# SCH_Auto-tune-FM-reciever-1_00_2024-02-2.net
KiCad netlist of a schematic drawn in EasyEDA
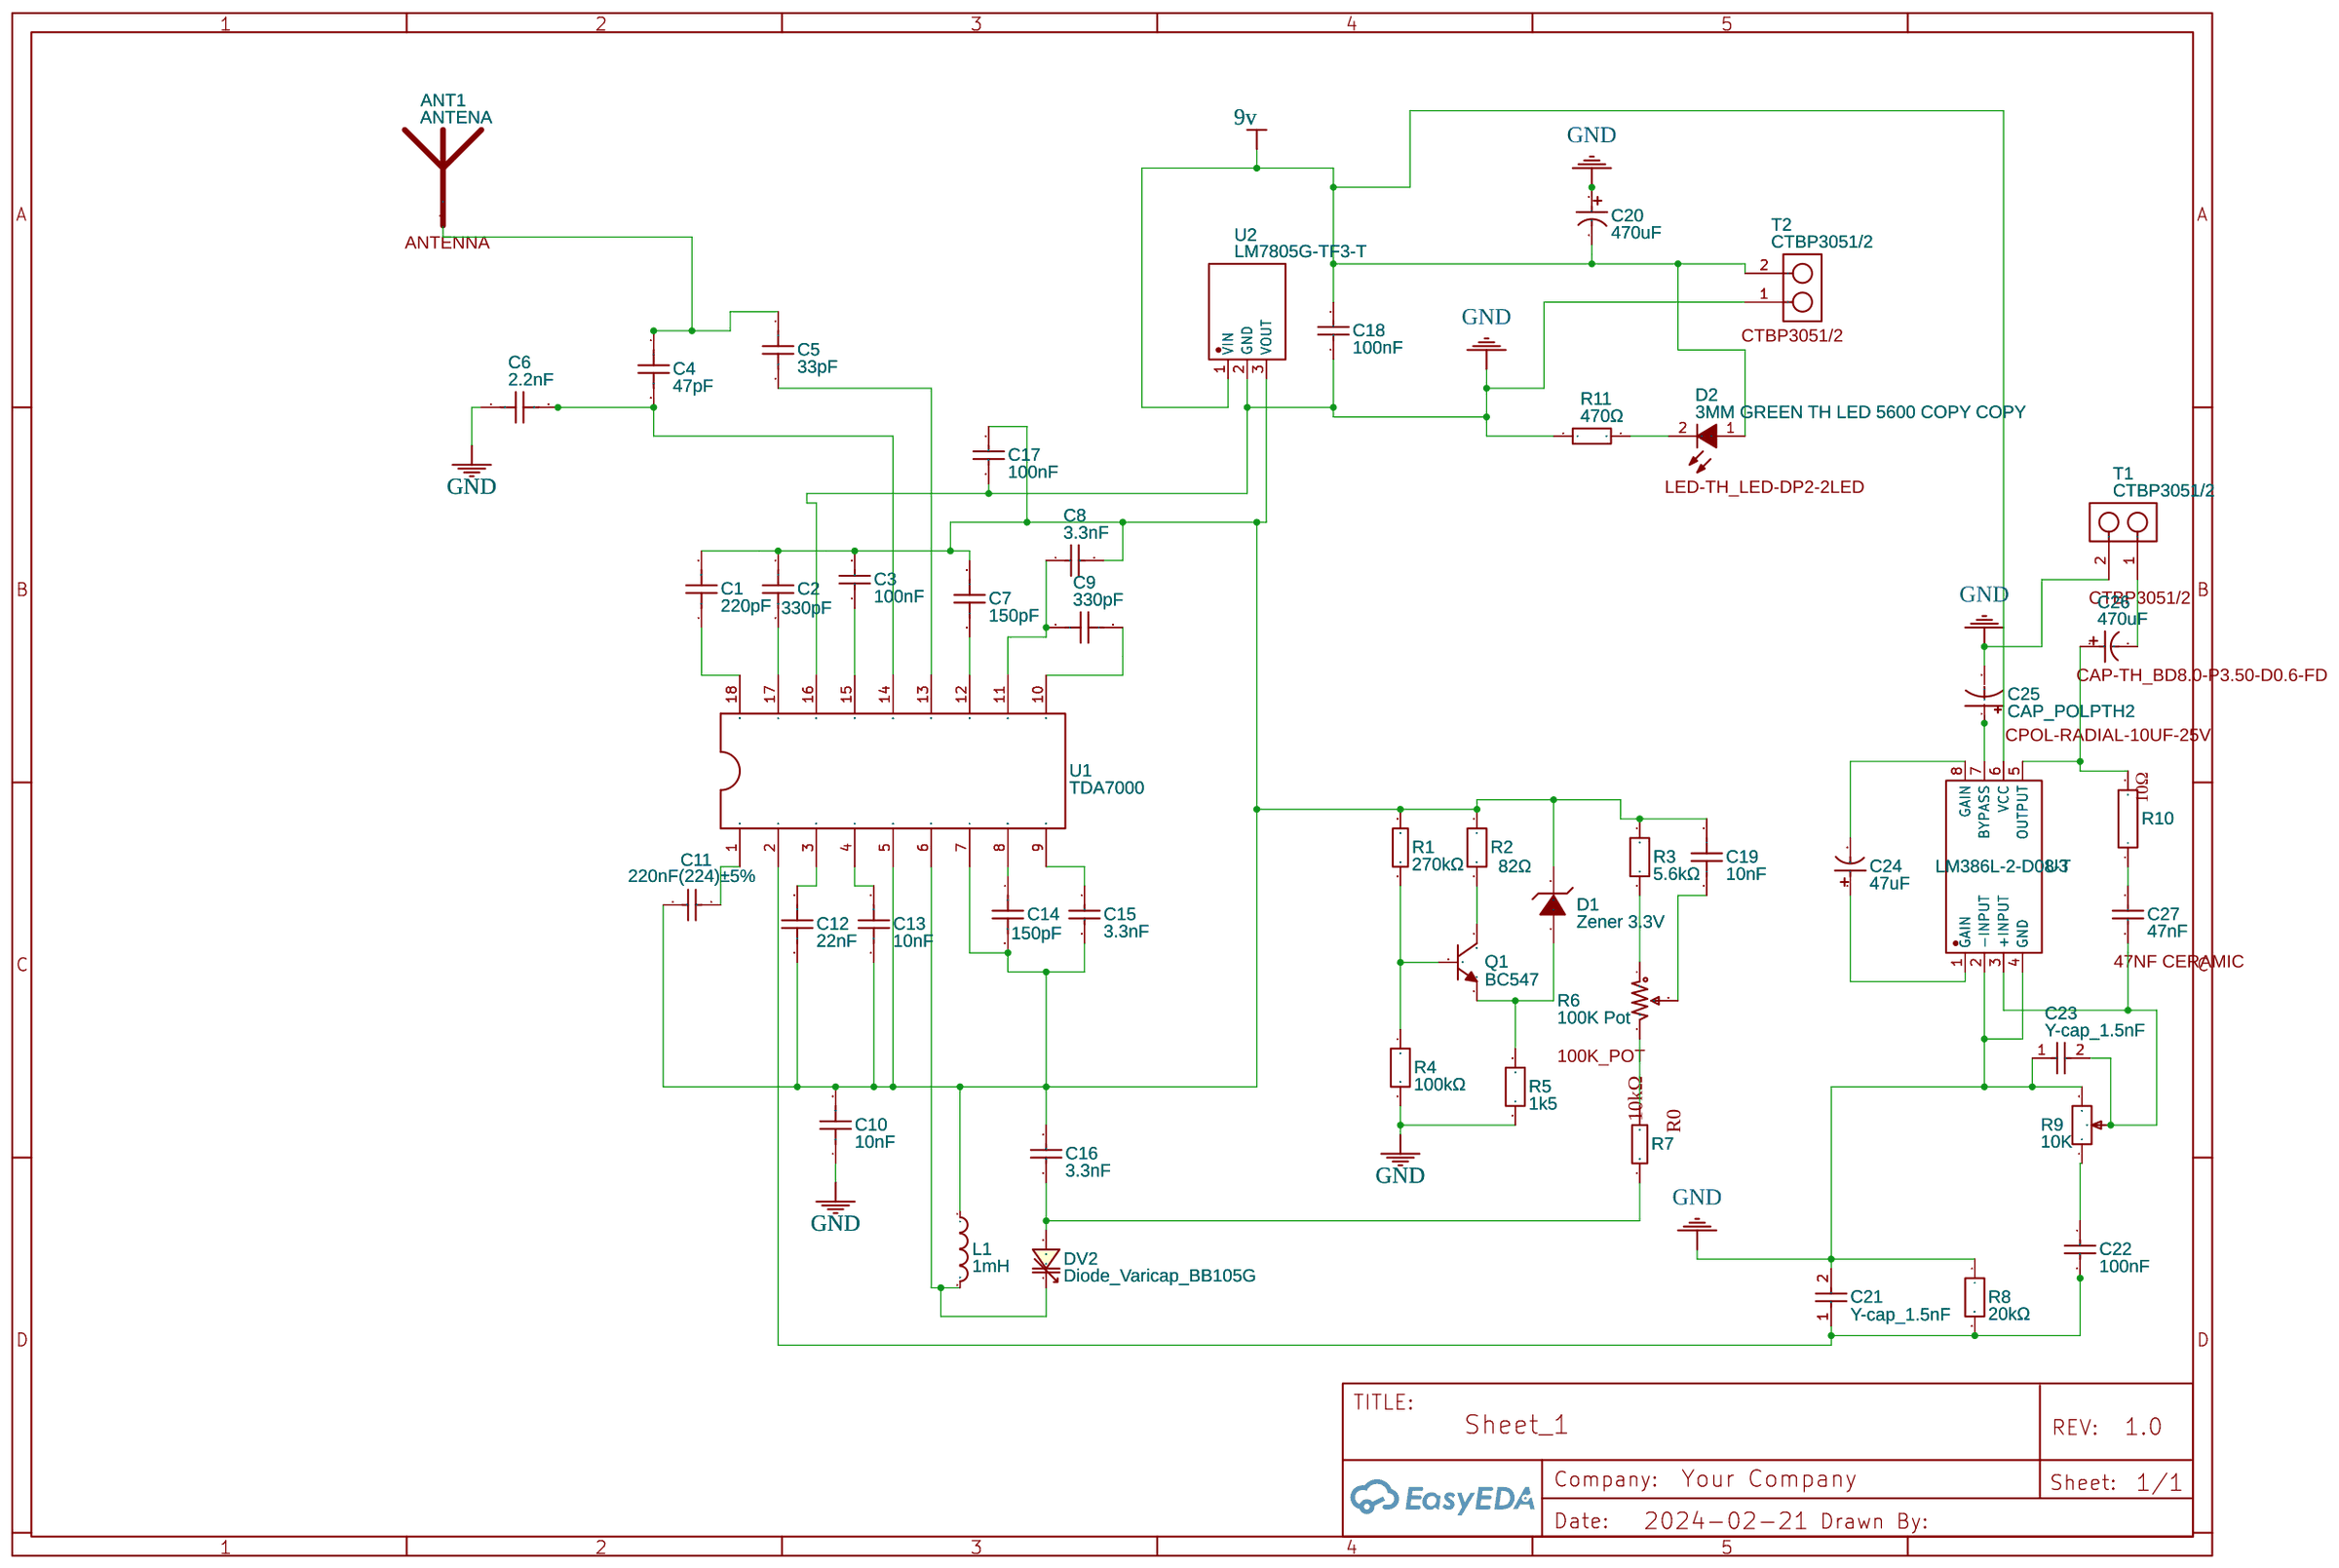
[diagram p0: schematic sheet]

(export (version "E")
  (design (tool "Eeschema 10.0.6"))
  (components
    (comp (ref "ANT1") (value "ANTENA") (libsource (lib "") (part "ANTENA")))
    (comp (ref "C1")
      (value "220pF")
      (fields (field (name "Manufacturer Part") "CT81N5Y5P1B221KSE") (field (name "Manufacturer") "FH(风华)"))
      (libsource (lib "") (part "CT81N5Y5P1B221KSE"))
    )
    (comp (ref "C2")
      (value "330pF")
      (fields
        (field (name "Manufacturer Part") "CC4-0805-CG-100V-330pF-J")
        (field (name "Manufacturer") "TORCH(火炬)")
      )
      (libsource (lib "") (part "CC4-0805-CG-100V-330PF-J"))
    )
    (comp (ref "C3")
      (value "100nF")
      (fields (field (name "Manufacturer Part") "0.1UF(104) +-20% 63v"))
      (libsource (lib "") (part "100nF"))
    )
    (comp (ref "C4")
      (value "47pF")
      (fields
        (field (name "Manufacturer Part") "CC4-0805-CG-50V-47pF-J")
        (field (name "Manufacturer") "TORCH(火炬)")
      )
      (libsource (lib "") (part "CC4-0805-CG -50V-47pF-J"))
    )
    (comp (ref "C5")
      (value "33pF")
      (fields
        (field (name "Manufacturer Part") "CC4-0805-CG-50V-33pF-J")
        (field (name "Manufacturer") "TORCH(火炬)")
      )
      (libsource (lib "") (part "CC4-0805-CG -50V-33pF-J"))
    )
    (comp (ref "C6")
      (value "2.2nF")
      (fields
        (field (name "Manufacturer Part") "CY1222ME1IEF47M0A2")
        (field (name "Manufacturer") "Dersonic(德尔创)")
      )
      (libsource (lib "") (part "CY1222ME1IEF47M0A2"))
    )
    (comp (ref "C7")
      (value "150pF")
      (fields
        (field (name "Manufacturer Part") "CC4-0805-CG-100V-150pF-J-L")
        (field (name "Manufacturer") "TORCH(火炬)")
      )
      (libsource (lib "") (part "CC4-0805-CG-100V-150PF-J-L"))
    )
    (comp (ref "C8")
      (value "3.3nF")
      (fields (field (name "Manufacturer Part") "332Z-50V-CCC") (field (name "Manufacturer") "LCSC"))
      (libsource (lib "") (part "3.3nF_1"))
    )
    (comp (ref "C9")
      (value "330pF")
      (fields
        (field (name "Manufacturer Part") "CC4-0805-CG-100V-330pF-J")
        (field (name "Manufacturer") "TORCH(火炬)")
      )
      (libsource (lib "") (part "CC4-0805-CG-100V-330PF-J_1"))
    )
    (comp (ref "C10")
      (value "10nF")
      (fields (field (name "Manufacturer Part") "MKS2C022201A00MSSD") (field (name "Manufacturer") "WIMA"))
      (libsource (lib "") (part "Capacitor 10nF #2"))
    )
    (comp (ref "C11")
      (value "220nF(224)±5%")
      (fields
        (field (name "Manufacturer Part") "CBBCapacitor 224J/630V")
        (field (name "Manufacturer") "ValuePro")
      )
      (libsource (lib "") (part "CBBCapacitor 224J/630V"))
    )
    (comp (ref "C12")
      (value "22nF")
      (fields (field (name "Manufacturer Part") "MKS2C022201A00MSSD") (field (name "Manufacturer") "WIMA"))
      (libsource (lib "") (part "Capacitor 22nF #7"))
    )
    (comp (ref "C13")
      (value "10nF")
      (fields (field (name "Manufacturer Part") "MKS2C022201A00MSSD") (field (name "Manufacturer") "WIMA"))
      (libsource (lib "") (part "Capacitor 10nF #2"))
    )
    (comp (ref "C14")
      (value "150pF")
      (fields
        (field (name "Manufacturer Part") "CC4-0805-CG-100V-150pF-J-L")
        (field (name "Manufacturer") "TORCH(火炬)")
      )
      (libsource (lib "") (part "CC4-0805-CG-100V-150PF-J-L"))
    )
    (comp (ref "C15")
      (value "3.3nF")
      (fields (field (name "Manufacturer Part") "332Z-50V-CCC") (field (name "Manufacturer") "LCSC"))
      (libsource (lib "") (part "3.3nF"))
    )
    (comp (ref "C16")
      (value "3.3nF")
      (fields (field (name "Manufacturer Part") "332Z-50V-CCC") (field (name "Manufacturer") "LCSC"))
      (libsource (lib "") (part "3.3nF"))
    )
    (comp (ref "C17")
      (value "100nF")
      (fields (field (name "Manufacturer Part") "0.1UF(104) +-20% 63v"))
      (libsource (lib "") (part "100nF"))
    )
    (comp (ref "C18")
      (value "100nF")
      (fields (field (name "Manufacturer Part") "0.1UF(104) +-20% 63v"))
      (libsource (lib "") (part "100nF"))
    )
    (comp (ref "C19")
      (value "10nF")
      (fields (field (name "Manufacturer Part") "MKS2C022201A00MSSD") (field (name "Manufacturer") "WIMA"))
      (libsource (lib "") (part "Capacitor 10nF #2"))
    )
    (comp (ref "C20")
      (value "470uF")
      (fields (field (name "Manufacturer Part") "470uf16v") (field (name "Manufacturer") "ValuePro"))
      (libsource (lib "") (part "470UF16V"))
    )
    (comp (ref "C21") (value "Y-cap_1.5nF") (libsource (lib "") (part "Y-cap_1.5nF_1")))
    (comp (ref "C22")
      (value "100nF")
      (fields (field (name "Manufacturer Part") "0.1UF(104) +-20% 63v"))
      (libsource (lib "") (part "100nF"))
    )
    (comp (ref "C23") (value "Y-cap_1.5nF") (libsource (lib "") (part "Y-cap_1.5nF")))
    (comp (ref "C24")
      (value "47uF")
      (fields (field (name "Manufacturer Part") "电解电容25V 47uF") (field (name "Manufacturer") "ValuePro"))
      (libsource (lib "") (part "CAPACITOR 47uF"))
    )
    (comp (ref "C25") (value "CAP_POLPTH2") (libsource (lib "") (part "CAP_POLPTH2")))
    (comp (ref "C26")
      (value "470uF")
      (fields
        (field (name "Manufacturer Part") "KM477M016F12RR0VH2FP0")
        (field (name "Manufacturer") "CX(承兴)")
      )
      (libsource (lib "") (part "470uf16v"))
    )
    (comp (ref "C27")
      (value "47nF")
      (fields (field (name "Manufacturer Part") "CT4-0805Y104M500") (field (name "Manufacturer") "LCSC"))
      (libsource (lib "") (part "47NF"))
    )
    (comp (ref "D1")
      (value "Zener 3.3V")
      (fields (field (name "Manufacturer Part") "Z7.5-CKD-3.3V@5mA"))
      (libsource (lib "") (part "Z7.5-CKD-3.3V@5MA"))
    )
    (comp (ref "D2")
      (value "3MM GREEN TH LED 5600 COPY COPY")
      (fields (field (name "Manufacturer Part") "5600") (field (name "Manufacturer") "VccLite"))
      (libsource (lib "") (part "3MM GREEN TH LED 5600 COPY COPY"))
    )
    (comp (ref "DV2") (value "Diode_Varicap_BB105G") (libsource (lib "") (part "Diode_Varicap_BB105G")))
    (comp (ref "L1")
      (value "1mH")
      (fields
        (field (name "Manufacturer Part") "CKL0510-1mH/K-A-0.252MHz T")
        (field (name "Manufacturer") "CENKER(岑科)")
      )
      (libsource (lib "") (part "CKL0510-1MH/K-A-0.252MHZ T"))
    )
    (comp (ref "Q1")
      (value "BC547")
      (fields (field (name "Manufacturer") "CJ(江苏长电/长晶)"))
      (libsource (lib "") (part "BC547"))
    )
    (comp (ref "R1")
      (value "270kΩ")
      (fields (field (name "Manufacturer Part") "MF3WS-270KΩ±1% T") (field (name "Manufacturer") "CCO(千志电子)"))
      (libsource (lib "") (part "MF3WS-270KΩ±1% T"))
    )
    (comp (ref "R2")
      (value "82Ω")
      (fields (field (name "Manufacturer Part") "23J82RE") (field (name "Manufacturer") "Ohmite"))
      (libsource (lib "") (part "23J82RE"))
    )
    (comp (ref "R3")
      (value "5.6kΩ")
      (fields (field (name "Manufacturer Part") "23J5K6E") (field (name "Manufacturer") "Ohmite"))
      (libsource (lib "") (part "23J5K6E"))
    )
    (comp (ref "R4")
      (value "100kΩ")
      (libsource (lib "") (part "AXIAL RESISTOR 100K OHM - TH_BD2.3-L6.0-P10.00-D0.4"))
    )
    (comp (ref "R5") (value "1k5") (libsource (lib "") (part "R_0603_EU")))
    (comp (ref "R6")
      (value "100K Pot")
      (fields (field (name "Manufacturer") "Amazon"))
      (libsource (lib "") (part "100K Pot"))
    )
    (comp (ref "R7")
      (value "Resistor 10KΩ")
      (fields (field (name "Manufacturer Part") "Resistor 10kΩ"))
      (libsource (lib "") (part "Resistor 10KΩ"))
    )
    (comp (ref "R8")
      (value "20kΩ")
      (fields (field (name "Manufacturer Part") "WHE20KJET") (field (name "Manufacturer") "Ohmite"))
      (libsource (lib "") (part "WHE20KJET"))
    )
    (comp (ref "R9")
      (value "10K")
      (fields (field (name "Manufacturer Part") "RK097111080J") (field (name "Manufacturer") "ALPS"))
      (libsource (lib "") (part "10kpotenc"))
    )
    (comp (ref "R10") (value "RESISTOR 10R/1W COPY") (libsource (lib "") (part "RESISTOR 10R/1W COPY")))
    (comp (ref "R11")
      (value "470Ω")
      (fields (field (name "Manufacturer Part") "MFR-25JT-52-470R") (field (name "Manufacturer") "YAGEO(国巨)"))
      (libsource (lib "") (part "MFR-25JT-52-470R"))
    )
    (comp (ref "T1")
      (value "CTBP3051/2")
      (fields (field (name "Manufacturer") "CAMDENBOSS"))
      (libsource (lib "") (part "CTBP3051/2_1"))
    )
    (comp (ref "T2")
      (value "CTBP3051/2")
      (fields (field (name "Manufacturer") "CAMDENBOSS"))
      (libsource (lib "") (part "CTBP3051/2"))
    )
    (comp (ref "U1") (value "TDA7000") (libsource (lib "") (part "TDA7000")))
    (comp (ref "U2")
      (value "LM7805G-TF3-T")
      (fields (field (name "Manufacturer") "UTC(友顺)"))
      (libsource (lib "") (part "LM7805G-TF3-T"))
    )
    (comp (ref "U3")
      (value "LM386L-2-D08-T")
      (fields (field (name "Manufacturer Part") "LM386L-D08-T") (field (name "Manufacturer") "UTC(友顺)"))
      (libsource (lib "") (part "LM386L-2-D08-T"))
    )
  )
  (nets
    (net (code "1") (name "9v") (class "Default")
      (node (ref "C18") (pin "1") (pinfunction "1_1") (pintype "input"))
      (node (ref "C20") (pin "2") (pinfunction "2_2") (pintype "input"))
      (node (ref "D2") (pin "1") (pinfunction "A_1") (pintype "input"))
      (node (ref "T2") (pin "2") (pinfunction "2_2") (pintype "unspecified"))
      (node (ref "U2") (pin "1") (pinfunction "VIN_1") (pintype "unspecified"))
      (node (ref "U3") (pin "6") (pinfunction "VCC_6") (pintype "unspecified"))
    )
    (net (code "2") (name "GND") (class "Default")
      (node (ref "C10") (pin "1") (pinfunction "1_1") (pintype "unspecified"))
      (node (ref "C17") (pin "2") (pinfunction "2_2") (pintype "input"))
      (node (ref "C18") (pin "2") (pinfunction "2_2") (pintype "input"))
      (node (ref "C20") (pin "1") (pinfunction "1_1") (pintype "input"))
      (node (ref "C21") (pin "2") (pinfunction "2_2") (pintype "input"))
      (node (ref "C23") (pin "1") (pinfunction "1_1") (pintype "input"))
      (node (ref "C25") (pin "2") (pinfunction "-_2") (pintype "bidirectional"))
      (node (ref "C6") (pin "1") (pinfunction "1_1") (pintype "unspecified"))
      (node (ref "R11") (pin "1") (pinfunction "1_1") (pintype "unspecified"))
      (node (ref "R4") (pin "2") (pinfunction "2_2") (pintype "unspecified"))
      (node (ref "R5") (pin "1") (pinfunction "1_1") (pintype "unspecified"))
      (node (ref "R8") (pin "1") (pinfunction "1_1") (pintype "unspecified"))
      (node (ref "R9") (pin "3") (pinfunction "3_3") (pintype "input"))
      (node (ref "T1") (pin "2") (pinfunction "2_2") (pintype "unspecified"))
      (node (ref "T2") (pin "1") (pinfunction "1_1") (pintype "unspecified"))
      (node (ref "U1") (pin "16") (pinfunction "16_16") (pintype "unspecified"))
      (node (ref "U2") (pin "2") (pinfunction "GND_2") (pintype "unspecified"))
      (node (ref "U3") (pin "2") (pinfunction "-INPUT_2") (pintype "unspecified"))
      (node (ref "U3") (pin "4") (pinfunction "GND_4") (pintype "unspecified"))
    )
    (net (code "3") (name "Net-(ANT1-Pad1)") (class "Default")
      (node (ref "ANT1") (pin "1") (pinfunction "1_1") (pintype "input"))
      (node (ref "C4") (pin "1") (pinfunction "1_1") (pintype "unspecified"))
      (node (ref "C5") (pin "1") (pinfunction "1_1") (pintype "unspecified"))
    )
    (net (code "4") (name "Net-(C1-Pad1)") (class "Default")
      (node (ref "C1") (pin "1") (pinfunction "1_1") (pintype "unspecified"))
      (node (ref "U1") (pin "18") (pinfunction "18_18") (pintype "unspecified"))
    )
    (net (code "5") (name "Net-(C2-Pad2)") (class "Default")
      (node (ref "C2") (pin "2") (pinfunction "2_2") (pintype "unspecified"))
      (node (ref "U1") (pin "17") (pinfunction "17_17") (pintype "unspecified"))
    )
    (net (code "6") (name "Net-(C3-Pad2)") (class "Default")
      (node (ref "C3") (pin "2") (pinfunction "2_2") (pintype "input"))
      (node (ref "U1") (pin "15") (pinfunction "15_15") (pintype "unspecified"))
    )
    (net (code "7") (name "Net-(C4-Pad2)") (class "Default")
      (node (ref "C4") (pin "2") (pinfunction "2_2") (pintype "unspecified"))
      (node (ref "C6") (pin "2") (pinfunction "2_2") (pintype "unspecified"))
      (node (ref "U1") (pin "14") (pinfunction "14_14") (pintype "unspecified"))
    )
    (net (code "8") (name "Net-(C5-Pad2)") (class "Default")
      (node (ref "C5") (pin "2") (pinfunction "2_2") (pintype "unspecified"))
      (node (ref "U1") (pin "13") (pinfunction "13_13") (pintype "unspecified"))
    )
    (net (code "9") (name "Net-(C7-Pad2)") (class "Default")
      (node (ref "C7") (pin "2") (pinfunction "2_2") (pintype "unspecified"))
      (node (ref "U1") (pin "12") (pinfunction "12_12") (pintype "unspecified"))
    )
    (net (code "10") (name "Net-(C8-Pad1)") (class "Default")
      (node (ref "C8") (pin "1") (pinfunction "1_1") (pintype "input"))
      (node (ref "C9") (pin "1") (pinfunction "1_1") (pintype "unspecified"))
      (node (ref "U1") (pin "11") (pinfunction "11_11") (pintype "unspecified"))
    )
    (net (code "11") (name "Net-(C9-Pad2)") (class "Default")
      (node (ref "C9") (pin "2") (pinfunction "2_2") (pintype "unspecified"))
      (node (ref "U1") (pin "10") (pinfunction "10_10") (pintype "unspecified"))
    )
    (net (code "12") (name "Net-(C11-Pad2)") (class "Default")
      (node (ref "C11") (pin "2") (pinfunction "2_2") (pintype "input"))
      (node (ref "U1") (pin "1") (pinfunction "1_1") (pintype "unspecified"))
    )
    (net (code "13") (name "Net-(C12-Pad2)") (class "Default")
      (node (ref "C12") (pin "2") (pinfunction "2_2") (pintype "unspecified"))
      (node (ref "U1") (pin "3") (pinfunction "3_3") (pintype "unspecified"))
    )
    (net (code "14") (name "Net-(C13-Pad2)") (class "Default")
      (node (ref "C13") (pin "2") (pinfunction "2_2") (pintype "unspecified"))
      (node (ref "U1") (pin "4") (pinfunction "4_4") (pintype "unspecified"))
    )
    (net (code "15") (name "Net-(C14-Pad1)") (class "Default")
      (node (ref "C14") (pin "1") (pinfunction "1_1") (pintype "unspecified"))
      (node (ref "U1") (pin "8") (pinfunction "8_8") (pintype "unspecified"))
    )
    (net (code "16") (name "Net-(C15-Pad1)") (class "Default")
      (node (ref "C15") (pin "1") (pinfunction "1_1") (pintype "input"))
      (node (ref "U1") (pin "9") (pinfunction "9_9") (pintype "unspecified"))
    )
    (net (code "17") (name "Net-(C19-Pad1)") (class "Default")
      (node (ref "C19") (pin "1") (pinfunction "1_1") (pintype "unspecified"))
      (node (ref "R6") (pin "2") (pinfunction "2_2") (pintype "unspecified"))
    )
    (net (code "18") (name "Net-(C21-Pad1)") (class "Default")
      (node (ref "C21") (pin "1") (pinfunction "1_1") (pintype "input"))
      (node (ref "C22") (pin "2") (pinfunction "2_2") (pintype "input"))
      (node (ref "R8") (pin "2") (pinfunction "2_2") (pintype "unspecified"))
      (node (ref "U1") (pin "2") (pinfunction "2_2") (pintype "unspecified"))
    )
    (net (code "19") (name "Net-(C22-Pad1)") (class "Default")
      (node (ref "C22") (pin "1") (pinfunction "1_1") (pintype "input"))
      (node (ref "R9") (pin "1") (pinfunction "1_1") (pintype "input"))
    )
    (net (code "20") (name "Net-(C24-Pad1)") (class "Default")
      (node (ref "C24") (pin "1") (pinfunction "1_1") (pintype "input"))
      (node (ref "U3") (pin "1") (pinfunction "GAIN_1") (pintype "unspecified"))
    )
    (net (code "21") (name "Net-(C24-Pad2)") (class "Default")
      (node (ref "C24") (pin "2") (pinfunction "2_2") (pintype "input"))
      (node (ref "U3") (pin "8") (pinfunction "GAIN_8") (pintype "unspecified"))
    )
    (net (code "22") (name "Net-(C25-+)") (class "Default")
      (node (ref "C25") (pin "1") (pinfunction "+_1") (pintype "bidirectional"))
      (node (ref "U3") (pin "7") (pinfunction "BYPASS_7") (pintype "unspecified"))
    )
    (net (code "23") (name "Net-(C26-Pad2)") (class "Default")
      (node (ref "C26") (pin "2") (pinfunction "2_2") (pintype "input"))
      (node (ref "T1") (pin "1") (pinfunction "1_1") (pintype "unspecified"))
    )
    (net (code "24") (name "Net-(C27-Pad1)") (class "Default")
      (node (ref "C27") (pin "1") (pinfunction "1_1") (pintype "input"))
      (node (ref "R10") (pin "1") (pinfunction "1_1") (pintype "unspecified"))
    )
    (net (code "25") (name "Net-(D1-A)") (class "Default")
      (node (ref "D1") (pin "1") (pinfunction "A_1") (pintype "unspecified"))
      (node (ref "Q1") (pin "3") (pinfunction "E_3") (pintype "unspecified"))
      (node (ref "R5") (pin "2") (pinfunction "2_2") (pintype "unspecified"))
    )
    (net (code "26") (name "Net-(D1-K)") (class "Default")
      (node (ref "C1") (pin "2") (pinfunction "2_2") (pintype "unspecified"))
      (node (ref "C10") (pin "2") (pinfunction "2_2") (pintype "unspecified"))
      (node (ref "C11") (pin "1") (pinfunction "1_1") (pintype "input"))
      (node (ref "C12") (pin "1") (pinfunction "1_1") (pintype "unspecified"))
      (node (ref "C13") (pin "1") (pinfunction "1_1") (pintype "unspecified"))
      (node (ref "C14") (pin "2") (pinfunction "2_2") (pintype "unspecified"))
      (node (ref "C15") (pin "2") (pinfunction "2_2") (pintype "input"))
      (node (ref "C16") (pin "1") (pinfunction "1_1") (pintype "input"))
      (node (ref "C17") (pin "1") (pinfunction "1_1") (pintype "input"))
      (node (ref "C19") (pin "2") (pinfunction "2_2") (pintype "unspecified"))
      (node (ref "C2") (pin "1") (pinfunction "1_1") (pintype "unspecified"))
      (node (ref "C3") (pin "1") (pinfunction "1_1") (pintype "input"))
      (node (ref "C7") (pin "1") (pinfunction "1_1") (pintype "unspecified"))
      (node (ref "C8") (pin "2") (pinfunction "2_2") (pintype "input"))
      (node (ref "D1") (pin "2") (pinfunction "K_2") (pintype "unspecified"))
      (node (ref "L1") (pin "1") (pinfunction "1_1") (pintype "unspecified"))
      (node (ref "R1") (pin "1") (pinfunction "1_1") (pintype "unspecified"))
      (node (ref "R2") (pin "1") (pinfunction "1_1") (pintype "unspecified"))
      (node (ref "R3") (pin "1") (pinfunction "1_1") (pintype "unspecified"))
      (node (ref "U1") (pin "5") (pinfunction "5_5") (pintype "unspecified"))
      (node (ref "U1") (pin "7") (pinfunction "7_7") (pintype "unspecified"))
      (node (ref "U2") (pin "3") (pinfunction "VOUT_3") (pintype "unspecified"))
    )
    (net (code "27") (name "Net-(D2-K)") (class "Default")
      (node (ref "D2") (pin "2") (pinfunction "K_2") (pintype "input"))
      (node (ref "R11") (pin "2") (pinfunction "2_2") (pintype "unspecified"))
    )
    (net (code "28") (name "Net-(DV2-A)") (class "Default")
      (node (ref "C16") (pin "2") (pinfunction "2_2") (pintype "input"))
      (node (ref "DV2") (pin "1") (pinfunction "A_1") (pintype "unspecified"))
      (node (ref "R7") (pin "2") (pinfunction "0_2") (pintype "input"))
    )
    (net (code "29") (name "Net-(DV2-K)") (class "Default")
      (node (ref "DV2") (pin "2") (pinfunction "K_2") (pintype "unspecified"))
      (node (ref "L1") (pin "2") (pinfunction "2_2") (pintype "unspecified"))
      (node (ref "U1") (pin "6") (pinfunction "6_6") (pintype "unspecified"))
    )
    (net (code "30") (name "Net-(Q1-B)") (class "Default")
      (node (ref "Q1") (pin "2") (pinfunction "B_2") (pintype "unspecified"))
      (node (ref "R1") (pin "2") (pinfunction "2_2") (pintype "unspecified"))
      (node (ref "R4") (pin "1") (pinfunction "1_1") (pintype "unspecified"))
    )
    (net (code "31") (name "Net-(Q1-C)") (class "Default")
      (node (ref "Q1") (pin "1") (pinfunction "C_1") (pintype "unspecified"))
      (node (ref "R2") (pin "2") (pinfunction "2_2") (pintype "unspecified"))
    )
    (net (code "32") (name "Net-(R3-Pad2)") (class "Default")
      (node (ref "R3") (pin "2") (pinfunction "2_2") (pintype "unspecified"))
      (node (ref "R6") (pin "1") (pinfunction "1_1") (pintype "unspecified"))
    )
    (net (code "33") (name "Net-(R6-Pad3)") (class "Default")
      (node (ref "R6") (pin "3") (pinfunction "3_3") (pintype "unspecified"))
      (node (ref "R7") (pin "1") (pinfunction "0_1") (pintype "input"))
    )
    (net (code "34") (name "Net-(U3-+INPUT)") (class "Default")
      (node (ref "C23") (pin "2") (pinfunction "2_2") (pintype "input"))
      (node (ref "C27") (pin "2") (pinfunction "2_2") (pintype "input"))
      (node (ref "R9") (pin "2") (pinfunction "2_2") (pintype "input"))
      (node (ref "U3") (pin "3") (pinfunction "+INPUT_3") (pintype "unspecified"))
    )
    (net (code "35") (name "Net-(U3-OUTPUT)") (class "Default")
      (node (ref "C26") (pin "1") (pinfunction "1_1") (pintype "input"))
      (node (ref "R10") (pin "2") (pinfunction "2_2") (pintype "unspecified"))
      (node (ref "U3") (pin "5") (pinfunction "OUTPUT_5") (pintype "unspecified"))
    )
  )
)
